# NFC_HackerCard.net
KiCad netlist of a schematic drawn in EasyEDA Pro
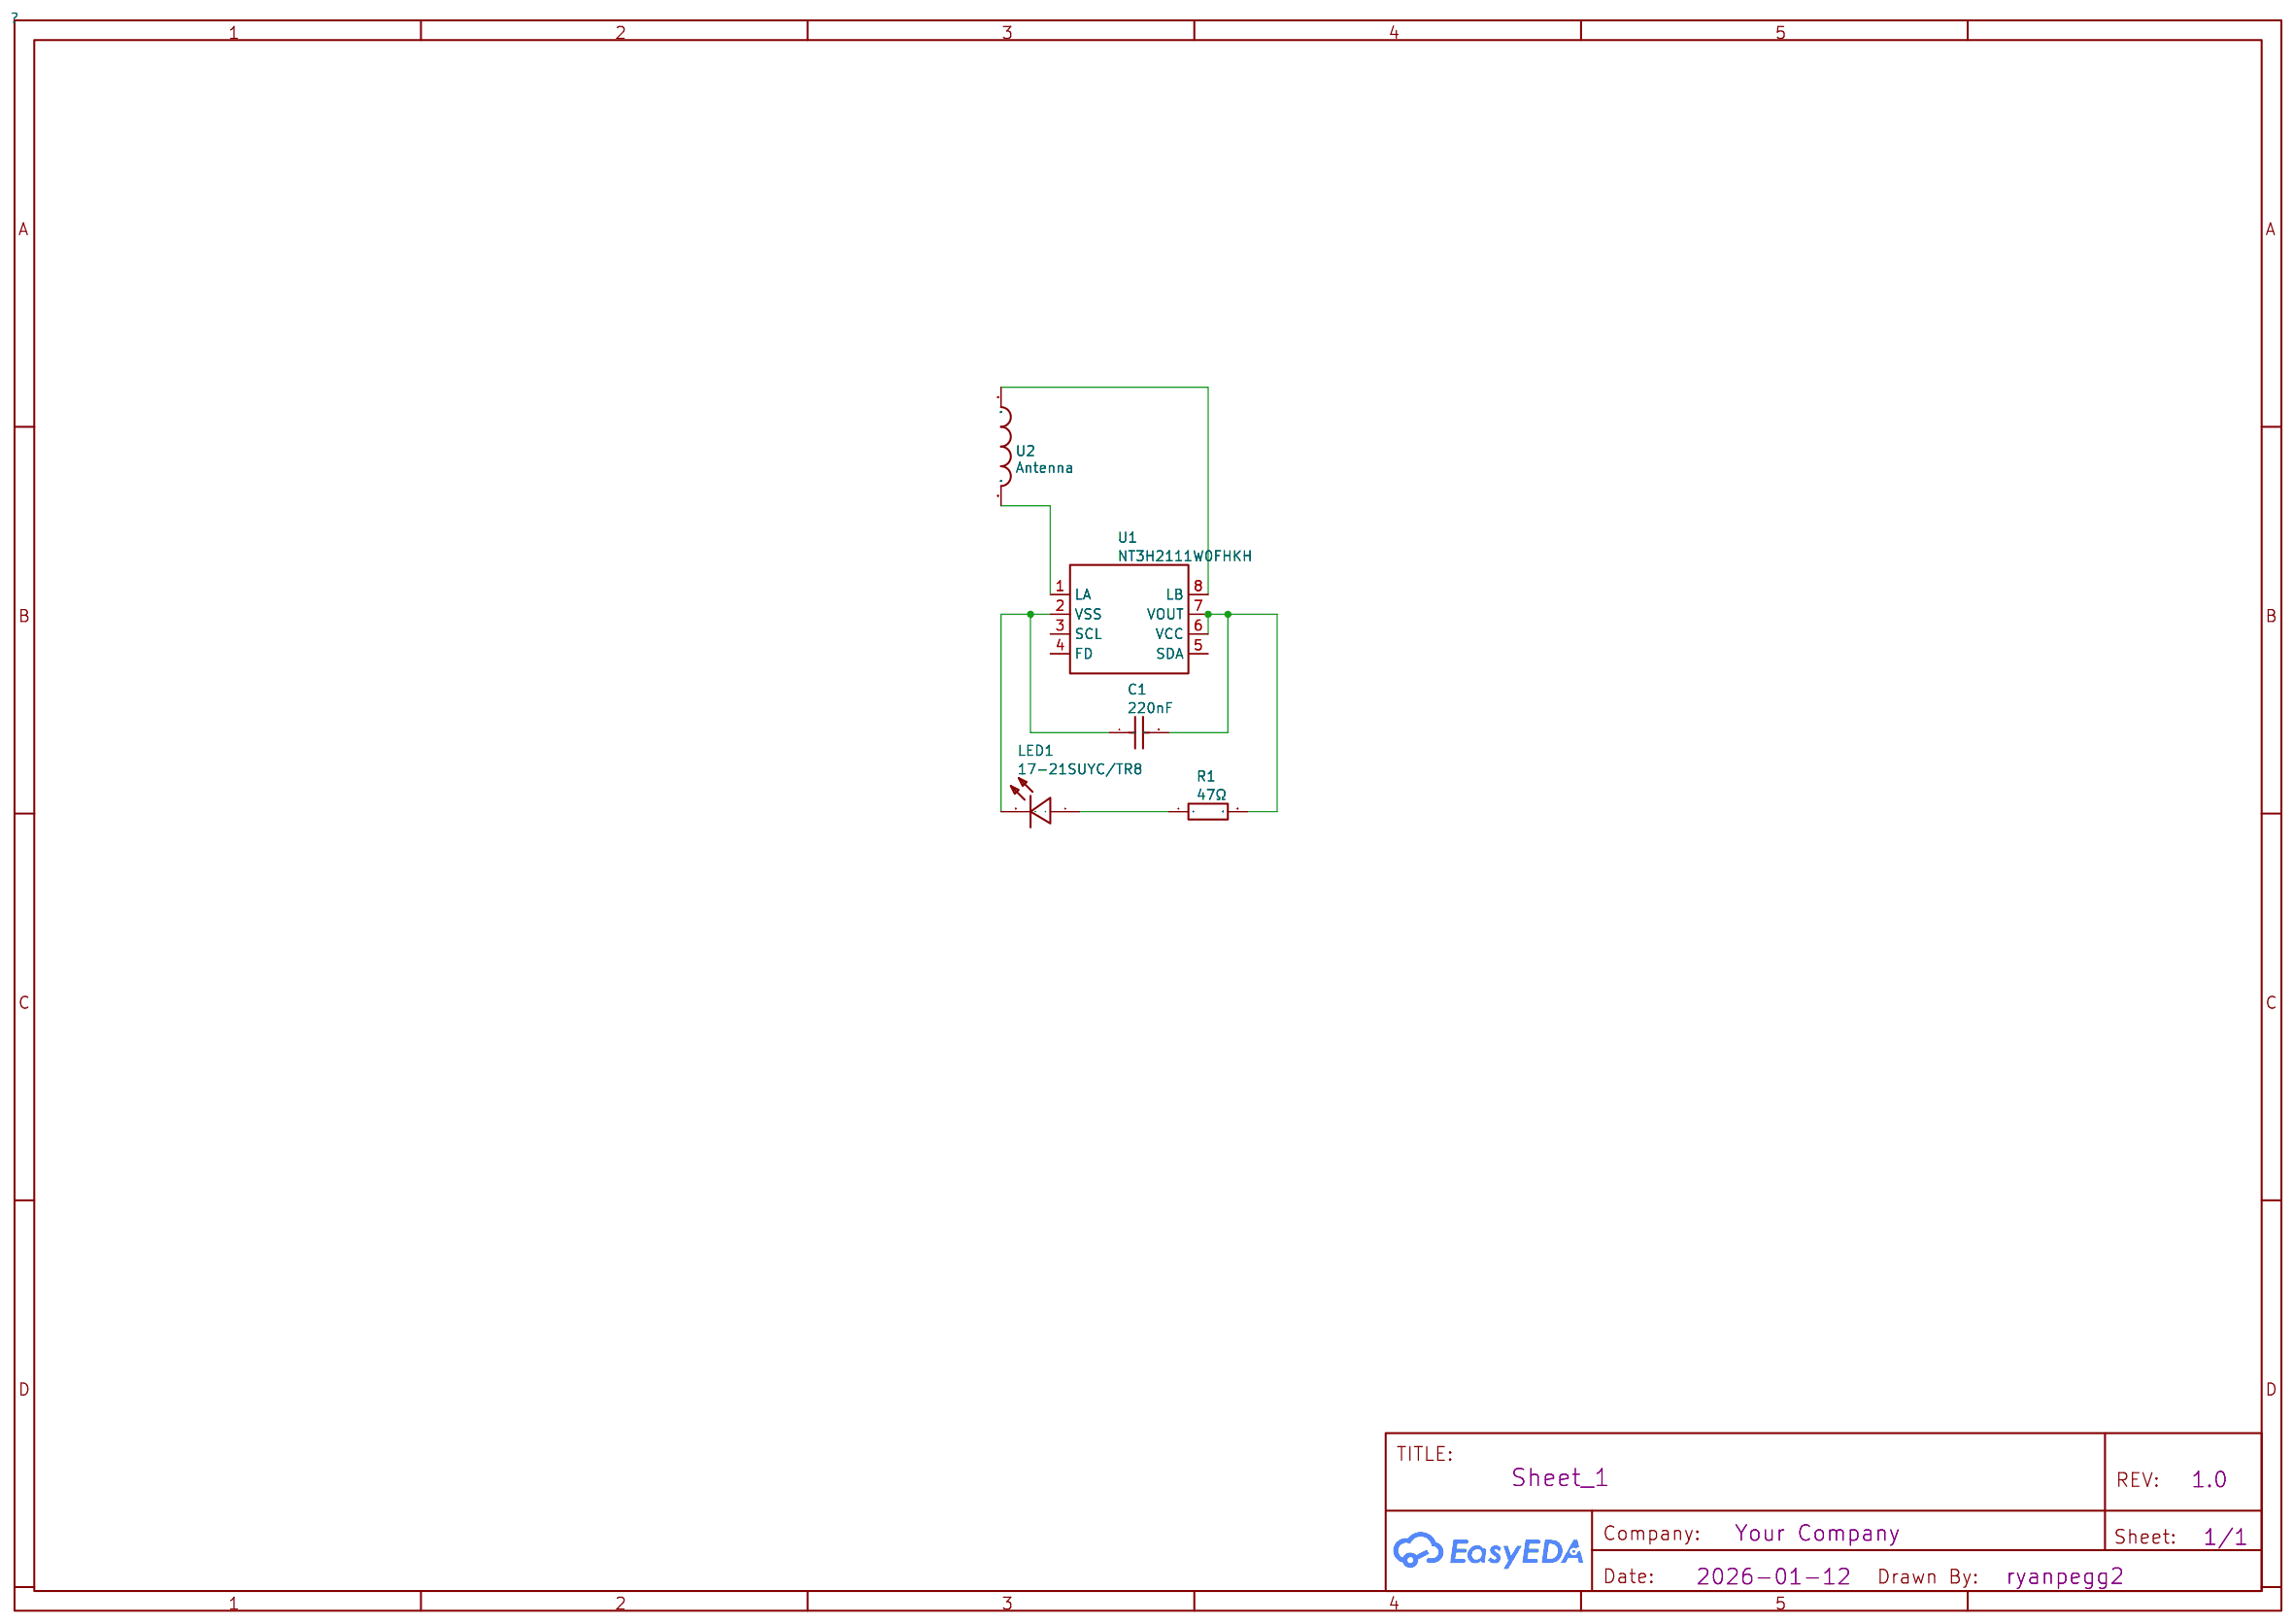
[diagram p0: schematic sheet]

(export (version "E")
  (design (tool "Eeschema 10.0.6"))
  (components
    (comp (ref "C1")
      (value "220nF")
      (footprint "easyedapro:C0603")
      (fields
        (field (name "Manufacturer Part") "CL10B224KA8NNNC")
        (field (name "Manufacturer") "SAMSUNG(三星)")
      )
      (libsource (lib "easyedapro") (part "220nF"))
    )
    (comp (ref "LED1")
      (value "17-21SUYC/TR8")
      (footprint "easyedapro:LED0805-R-RD")
      (fields (field (name "Manufacturer Part") "KT-0805黄灯") (field (name "Manufacturer") "KENTO"))
      (libsource (lib "easyedapro") (part "17-21SUYC/TR8"))
    )
    (comp (ref "R1")
      (value "47Ω")
      (footprint "easyedapro:R0603")
      (fields
        (field (name "Manufacturer Part") "0603WAF470JT5E")
        (field (name "Manufacturer") "UNI-ROYAL(厚声)")
      )
      (libsource (lib "easyedapro") (part "47Ω"))
    )
    (comp (ref "U1")
      (value "NT3H2111W0FHKH")
      (footprint "easyedapro:XQFN-8_L1.6-W1.6-P0.50-BL_NT3H2111W0FHKH")
      (fields (field (name "Manufacturer") "NXP(恩智浦)") (field (name "Contributor") "LCSC"))
      (libsource (lib "easyedapro") (part "NT3H2111W0FHKH"))
    )
    (comp (ref "U2")
      (value "Antenna")
      (footprint "easyedapro:25X48MM_NFC_ANTENNA")
      (fields (field (name "Contributor") "maggie.j.liu"))
      (libsource (lib "easyedapro") (part "Antenna"))
    )
  )
  (nets
    (net (code "1") (name "Net-(LED1-+)") (class "Default")
      (node (ref "LED1") (pin "1") (pinfunction "+_1") (pintype "unspecified"))
      (node (ref "R1") (pin "1") (pinfunction "1_1") (pintype "input"))
    )
    (net (code "2") (name "Net-(LED1--)") (class "Default")
      (node (ref "C1") (pin "1") (pinfunction "1_1") (pintype "input"))
      (node (ref "LED1") (pin "2") (pinfunction "-_2") (pintype "unspecified"))
      (node (ref "U1") (pin "2") (pinfunction "VSS_2") (pintype "unspecified"))
    )
    (net (code "3") (name "Net-(U1-LA)") (class "Default")
      (node (ref "U1") (pin "1") (pinfunction "LA_1") (pintype "unspecified"))
      (node (ref "U2") (pin "P$1") (pinfunction "P$1_P$1") (pintype "unspecified"))
    )
    (net (code "4") (name "Net-(U1-LB)") (class "Default")
      (node (ref "U1") (pin "8") (pinfunction "LB_8") (pintype "unspecified"))
      (node (ref "U2") (pin "P$2") (pinfunction "P$2_P$2") (pintype "unspecified"))
    )
    (net (code "5") (name "Net-(U1-VCC)") (class "Default")
      (node (ref "C1") (pin "2") (pinfunction "2_2") (pintype "input"))
      (node (ref "R1") (pin "2") (pinfunction "2_2") (pintype "input"))
      (node (ref "U1") (pin "6") (pinfunction "VCC_6") (pintype "unspecified"))
      (node (ref "U1") (pin "7") (pinfunction "VOUT_7") (pintype "unspecified"))
    )
    (net (code "6") (name "unconnected-(U1-FD-Pad4)") (class "Default")
      (node (ref "U1") (pin "4") (pinfunction "FD_4") (pintype "unspecified"))
    )
    (net (code "7") (name "unconnected-(U1-SCL-Pad3)") (class "Default")
      (node (ref "U1") (pin "3") (pinfunction "SCL_3") (pintype "unspecified"))
    )
    (net (code "8") (name "unconnected-(U1-SDA-Pad5)") (class "Default")
      (node (ref "U1") (pin "5") (pinfunction "SDA_5") (pintype "unspecified"))
    )
  )
)
